# power-reset_button_board.net
KiCad netlist of a schematic drawn in EAGLE
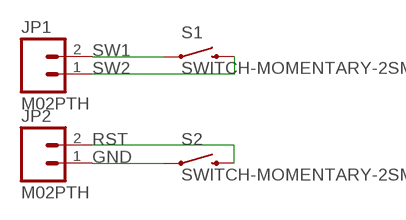
[diagram p0: schematic, sheet 1]

(export (version "E")
  (design (tool "Eeschema 10.0.6"))
  (components
    (comp (ref "JP1")
      (value "M02PTH")
      (footprint "eagle-import:1X02")
      (libsource (lib "eagle-import") (part "M02PTH"))
    )
    (comp (ref "JP2")
      (value "M02PTH")
      (footprint "eagle-import:1X02")
      (libsource (lib "eagle-import") (part "M02PTH"))
    )
    (comp (ref "S1")
      (value "SWITCH-MOMENTARY-2SMD")
      (footprint "eagle-import:TACTILE-SWITCH-SMD")
      (libsource (lib "eagle-import") (part "SWITCH-MOMENTARY-2SMD"))
    )
    (comp (ref "S2")
      (value "SWITCH-MOMENTARY-2SMD")
      (footprint "eagle-import:TACTILE-SWITCH-SMD")
      (libsource (lib "eagle-import") (part "SWITCH-MOMENTARY-2SMD"))
    )
  )
  (nets
    (net (code "1") (name "/GND") (class "Default")
      (node (ref "JP2") (pin "1") (pinfunction "1_1") (pintype "passive"))
      (node (ref "S2") (pin "1") (pinfunction "1_1") (pintype "passive"))
    )
    (net (code "2") (name "/RST") (class "Default")
      (node (ref "JP2") (pin "2") (pinfunction "2_2") (pintype "passive"))
      (node (ref "S2") (pin "3") (pinfunction "2_3") (pintype "passive"))
    )
    (net (code "3") (name "/SW1") (class "Default")
      (node (ref "JP1") (pin "2") (pinfunction "2_2") (pintype "passive"))
      (node (ref "S1") (pin "1") (pinfunction "1_1") (pintype "passive"))
    )
    (net (code "4") (name "/SW2") (class "Default")
      (node (ref "JP1") (pin "1") (pinfunction "1_1") (pintype "passive"))
      (node (ref "S1") (pin "3") (pinfunction "2_3") (pintype "passive"))
    )
  )
)
